# Actuator_control_v6.net
KiCad netlist of a schematic drawn in EAGLE
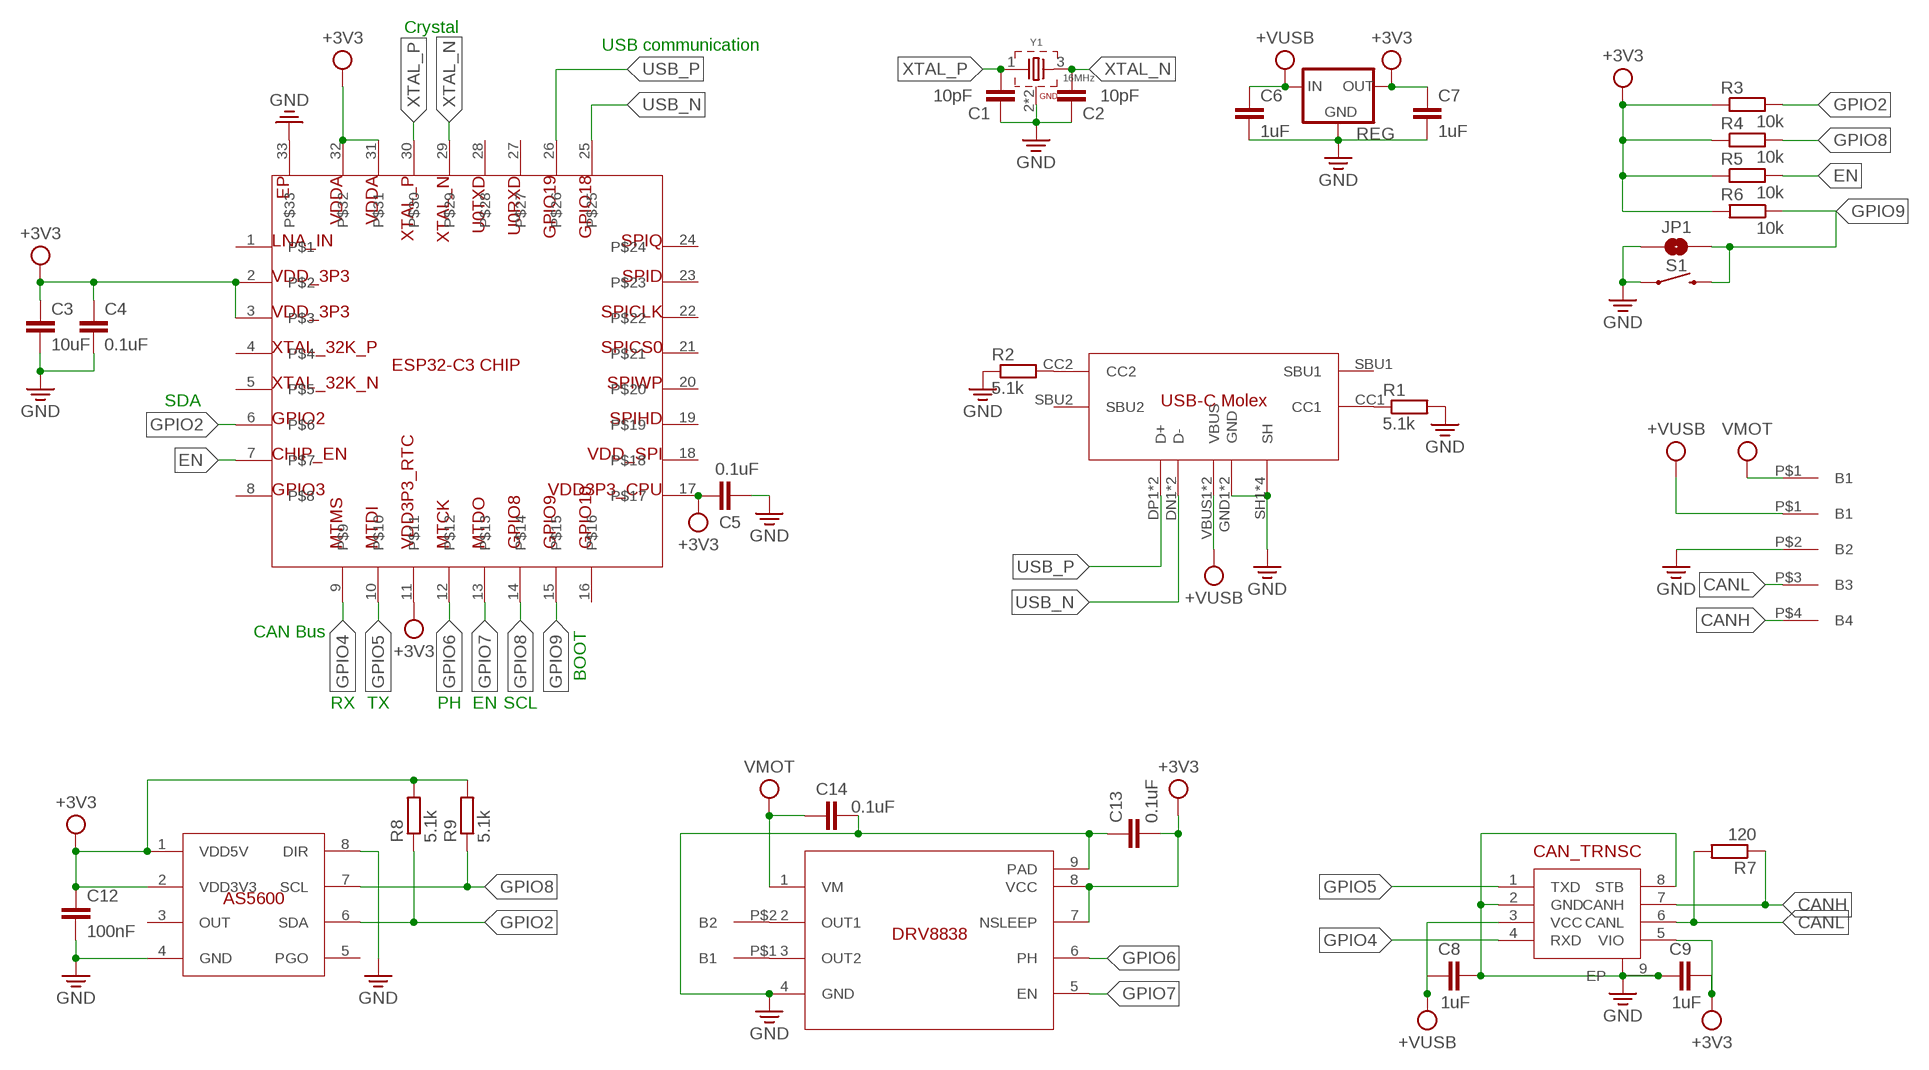
[diagram p0: schematic, sheet 1]

(export (version "E")
  (design (tool "Eeschema 10.0.6"))
  (components
    (comp (ref "AS5600")
      (value "AS5600")
      (footprint "eagle-import:SOIC127P600X175-8N")
      (libsource (lib "eagle-import") (part "AS5600"))
    )
    (comp (ref "C1")
      (value "10pF")
      (footprint "eagle-import:C0402")
      (libsource (lib "eagle-import") (part "C-EUC0402"))
    )
    (comp (ref "C2")
      (value "10pF")
      (footprint "eagle-import:C0402")
      (libsource (lib "eagle-import") (part "C-EUC0402"))
    )
    (comp (ref "C3")
      (value "10uF")
      (footprint "eagle-import:C0402")
      (libsource (lib "eagle-import") (part "C-EUC0402"))
    )
    (comp (ref "C4")
      (value "0.1uF")
      (footprint "eagle-import:C0402")
      (libsource (lib "eagle-import") (part "C-EUC0402"))
    )
    (comp (ref "C5")
      (value "0.1uF")
      (footprint "eagle-import:C0402")
      (libsource (lib "eagle-import") (part "C-EUC0402"))
    )
    (comp (ref "C6")
      (value "1uF")
      (footprint "eagle-import:C0402")
      (libsource (lib "eagle-import") (part "C-EUC0402"))
    )
    (comp (ref "C7")
      (value "1uF")
      (footprint "eagle-import:C0402")
      (libsource (lib "eagle-import") (part "C-EUC0402"))
    )
    (comp (ref "C8")
      (value "1uF")
      (footprint "eagle-import:C0402")
      (libsource (lib "eagle-import") (part "C-EUC0402"))
    )
    (comp (ref "C9")
      (value "1uF")
      (footprint "eagle-import:C0402")
      (libsource (lib "eagle-import") (part "C-EUC0402"))
    )
    (comp (ref "C12")
      (value "100nF")
      (footprint "eagle-import:C0402")
      (libsource (lib "eagle-import") (part "C-EUC0402"))
    )
    (comp (ref "C13")
      (value "0.1uF")
      (footprint "eagle-import:C0402")
      (libsource (lib "eagle-import") (part "C-EUC0402"))
    )
    (comp (ref "C14")
      (value "0.1uF")
      (footprint "eagle-import:C0402")
      (libsource (lib "eagle-import") (part "C-EUC0402"))
    )
    (comp (ref "CAN")
      (value "CAN_TRNSC")
      (footprint "eagle-import:SON65P300X300X75-9T160X240N")
      (libsource (lib "eagle-import") (part "CAN_TRNSC"))
    )
    (comp (ref "DRV8838")
      (value "DRV8838")
      (footprint "eagle-import:SON50P200X200X80-9T90X160N")
      (libsource (lib "eagle-import") (part "DRV8838"))
    )
    (comp (ref "ESP32")
      (value "ESP32-C3CHIP")
      (footprint "eagle-import:ESP32-C3_CHIP")
      (libsource (lib "eagle-import") (part "ESP32-C3CHIP"))
    )
    (comp (ref "JP1")
      (value "JUMPER-SMT_2_NO_SILK")
      (footprint "eagle-import:SMT-JUMPER_2_NO_SILK")
      (libsource (lib "eagle-import") (part "JUMPER-SMT_2_NO_SILK"))
    )
    (comp (ref "R1")
      (value "5.1k")
      (footprint "eagle-import:R0402")
      (libsource (lib "eagle-import") (part "R-EU_R0402"))
    )
    (comp (ref "R2")
      (value "5.1k")
      (footprint "eagle-import:R0402")
      (libsource (lib "eagle-import") (part "R-EU_R0402"))
    )
    (comp (ref "R3")
      (value "10k")
      (footprint "eagle-import:R0402")
      (libsource (lib "eagle-import") (part "R-EU_R0402"))
    )
    (comp (ref "R4")
      (value "10k")
      (footprint "eagle-import:R0402")
      (libsource (lib "eagle-import") (part "R-EU_R0402"))
    )
    (comp (ref "R5")
      (value "10k")
      (footprint "eagle-import:R0402")
      (libsource (lib "eagle-import") (part "R-EU_R0402"))
    )
    (comp (ref "R6")
      (value "10k")
      (footprint "eagle-import:R0402")
      (libsource (lib "eagle-import") (part "R-EU_R0402"))
    )
    (comp (ref "R7")
      (value "120")
      (footprint "eagle-import:R0402")
      (libsource (lib "eagle-import") (part "R-EU_R0402"))
    )
    (comp (ref "R8")
      (value "5.1k")
      (footprint "eagle-import:R0402")
      (libsource (lib "eagle-import") (part "R-EU_R0402"))
    )
    (comp (ref "R9")
      (value "5.1k")
      (footprint "eagle-import:R0402")
      (libsource (lib "eagle-import") (part "R-EU_R0402"))
    )
    (comp (ref "REG")
      (value "XC63FPM")
      (footprint "eagle-import:SOT23")
      (libsource (lib "eagle-import") (part "XC63FPM"))
    )
    (comp (ref "S1")
      (value "MOMENTARY-SWITCH-SPST-SMD-6.0X3.5MM")
      (footprint "eagle-import:TACTILE_SWITCH_SMD_6.0X3.5MM")
      (libsource (lib "eagle-import") (part "MOMENTARY-SWITCH-SPST-SMD-6.0X3.5MM"))
    )
    (comp (ref "U$3")
      (value "USB-CMOLEX")
      (footprint "eagle-import:USB-CMOLEX")
      (libsource (lib "eagle-import") (part "USB-CMOLEX"))
    )
    (comp (ref "U$6")
      (value "BREAKOUT_44-SMD2.54")
      (footprint "eagle-import:BREAKOUT_4_SMD_2.54")
      (libsource (lib "eagle-import") (part "BREAKOUT_44-SMD2.54"))
    )
    (comp (ref "U$7")
      (value "BREAKOUT_11-SMD-2.54")
      (footprint "eagle-import:BREAKOUT_1_SMD_2.54")
      (libsource (lib "eagle-import") (part "BREAKOUT_11-SMD-2.54"))
    )
    (comp (ref "U$8")
      (value "BREAKOUT_22-THT")
      (footprint "eagle-import:BREAKOUT_2_THT")
      (libsource (lib "eagle-import") (part "BREAKOUT_22-THT"))
    )
    (comp (ref "Y1")
      (value "16MHz")
      (footprint "eagle-import:WE-XTAL_CFPX-180")
      (fields (field (name "TOLERANCE") "±50ppm"))
      (libsource (lib "eagle-import") (part "WE-XTAL_CFPX-180_830035264"))
    )
  )
  (nets
    (net (code "1") (name "+3V3") (class "Default")
      (node (ref "AS5600") (pin "1") (pinfunction "VDD5V_1") (pintype "power_in"))
      (node (ref "AS5600") (pin "2") (pinfunction "VDD3V3_2") (pintype "power_in"))
      (node (ref "C12") (pin "1") (pinfunction "1_1") (pintype "passive"))
      (node (ref "C13") (pin "2") (pinfunction "2_2") (pintype "passive"))
      (node (ref "C3") (pin "1") (pinfunction "1_1") (pintype "passive"))
      (node (ref "C4") (pin "1") (pinfunction "1_1") (pintype "passive"))
      (node (ref "C5") (pin "2") (pinfunction "2_2") (pintype "passive"))
      (node (ref "C7") (pin "1") (pinfunction "1_1") (pintype "passive"))
      (node (ref "C9") (pin "2") (pinfunction "2_2") (pintype "passive"))
      (node (ref "CAN") (pin "5") (pinfunction "VIO_5") (pintype "bidirectional"))
      (node (ref "DRV8838") (pin "7") (pinfunction "NSLEEP_7") (pintype "bidirectional"))
      (node (ref "DRV8838") (pin "8") (pinfunction "VCC_8") (pintype "bidirectional"))
      (node (ref "ESP32") (pin "11") (pinfunction "P$11_11") (pintype "bidirectional"))
      (node (ref "ESP32") (pin "17") (pinfunction "P$17_17") (pintype "bidirectional"))
      (node (ref "ESP32") (pin "2") (pinfunction "P$2_2") (pintype "bidirectional"))
      (node (ref "ESP32") (pin "3") (pinfunction "P$3_3") (pintype "bidirectional"))
      (node (ref "ESP32") (pin "31") (pinfunction "P$31_31") (pintype "bidirectional"))
      (node (ref "ESP32") (pin "32") (pinfunction "P$32_32") (pintype "bidirectional"))
      (node (ref "R3") (pin "1") (pinfunction "1_1") (pintype "passive"))
      (node (ref "R4") (pin "1") (pinfunction "1_1") (pintype "passive"))
      (node (ref "R5") (pin "1") (pinfunction "1_1") (pintype "passive"))
      (node (ref "R6") (pin "2") (pinfunction "2_2") (pintype "passive"))
      (node (ref "R8") (pin "2") (pinfunction "2_2") (pintype "passive"))
      (node (ref "R9") (pin "2") (pinfunction "2_2") (pintype "passive"))
      (node (ref "REG") (pin "2") (pinfunction "OUT_2") (pintype "passive"))
    )
    (net (code "2") (name "+VUSB") (class "Default")
      (node (ref "C6") (pin "1") (pinfunction "1_1") (pintype "passive"))
      (node (ref "C8") (pin "1") (pinfunction "1_1") (pintype "passive"))
      (node (ref "CAN") (pin "3") (pinfunction "VCC_3") (pintype "power_in"))
      (node (ref "REG") (pin "3") (pinfunction "IN_3") (pintype "input"))
      (node (ref "U$3") (pin "VBUS1") (pinfunction "VBUS_VBUS1") (pintype "power_in"))
      (node (ref "U$3") (pin "VBUS2") (pinfunction "VBUS_VBUS2") (pintype "power_in"))
      (node (ref "U$6") (pin "P$1") (pinfunction "B1_P$1") (pintype "bidirectional"))
    )
    (net (code "3") (name "/OUT") (class "Default")
      (node (ref "AS5600") (pin "3") (pinfunction "OUT_3") (pintype "power_in"))
    )
    (net (code "4") (name "/PGO") (class "Default")
      (node (ref "AS5600") (pin "5") (pinfunction "PGO_5") (pintype "power_in"))
    )
    (net (code "5") (name "CANH") (class "Default")
      (node (ref "CAN") (pin "7") (pinfunction "CANH_7") (pintype "bidirectional"))
      (node (ref "R7") (pin "1") (pinfunction "1_1") (pintype "passive"))
      (node (ref "U$6") (pin "P$4") (pinfunction "B4_P$4") (pintype "bidirectional"))
    )
    (net (code "6") (name "CANL") (class "Default")
      (node (ref "CAN") (pin "6") (pinfunction "CANL_6") (pintype "bidirectional"))
      (node (ref "R7") (pin "2") (pinfunction "2_2") (pintype "passive"))
      (node (ref "U$6") (pin "P$3") (pinfunction "B3_P$3") (pintype "bidirectional"))
    )
    (net (code "7") (name "EN") (class "Default")
      (node (ref "ESP32") (pin "7") (pinfunction "P$7_7") (pintype "bidirectional"))
      (node (ref "R5") (pin "2") (pinfunction "2_2") (pintype "passive"))
    )
    (net (code "8") (name "GND") (class "Default")
      (node (ref "AS5600") (pin "4") (pinfunction "GND_4") (pintype "power_in"))
      (node (ref "AS5600") (pin "8") (pinfunction "DIR_8") (pintype "power_in"))
      (node (ref "C1") (pin "1") (pinfunction "1_1") (pintype "passive"))
      (node (ref "C12") (pin "2") (pinfunction "2_2") (pintype "passive"))
      (node (ref "C13") (pin "1") (pinfunction "1_1") (pintype "passive"))
      (node (ref "C14") (pin "2") (pinfunction "2_2") (pintype "passive"))
      (node (ref "C2") (pin "1") (pinfunction "1_1") (pintype "passive"))
      (node (ref "C3") (pin "2") (pinfunction "2_2") (pintype "passive"))
      (node (ref "C4") (pin "2") (pinfunction "2_2") (pintype "passive"))
      (node (ref "C5") (pin "1") (pinfunction "1_1") (pintype "passive"))
      (node (ref "C6") (pin "2") (pinfunction "2_2") (pintype "passive"))
      (node (ref "C7") (pin "2") (pinfunction "2_2") (pintype "passive"))
      (node (ref "C8") (pin "2") (pinfunction "2_2") (pintype "passive"))
      (node (ref "C9") (pin "1") (pinfunction "1_1") (pintype "passive"))
      (node (ref "CAN") (pin "2") (pinfunction "GND_2") (pintype "power_in"))
      (node (ref "CAN") (pin "8") (pinfunction "STB_8") (pintype "bidirectional"))
      (node (ref "CAN") (pin "9") (pinfunction "EP_9") (pintype "power_in"))
      (node (ref "DRV8838") (pin "4") (pinfunction "GND_4") (pintype "bidirectional"))
      (node (ref "DRV8838") (pin "9") (pinfunction "PAD_9") (pintype "bidirectional"))
      (node (ref "ESP32") (pin "33") (pinfunction "P$33_33") (pintype "bidirectional"))
      (node (ref "JP1") (pin "1") (pinfunction "1_1") (pintype "passive"))
      (node (ref "R1") (pin "2") (pinfunction "2_2") (pintype "passive"))
      (node (ref "R2") (pin "1") (pinfunction "1_1") (pintype "passive"))
      (node (ref "REG") (pin "1") (pinfunction "GND_1") (pintype "input"))
      (node (ref "S1") (pin "1") (pinfunction "1_1") (pintype "passive"))
      (node (ref "U$3") (pin "GND1") (pinfunction "GND_GND1") (pintype "power_in"))
      (node (ref "U$3") (pin "GND2") (pinfunction "GND_GND2") (pintype "power_in"))
      (node (ref "U$3") (pin "SH1") (pinfunction "SH_SH1") (pintype "power_in"))
      (node (ref "U$3") (pin "SH2") (pinfunction "SH_SH2") (pintype "power_in"))
      (node (ref "U$3") (pin "SH3") (pinfunction "SH_SH3") (pintype "power_in"))
      (node (ref "U$3") (pin "SH4") (pinfunction "SH_SH4") (pintype "power_in"))
      (node (ref "U$6") (pin "P$2") (pinfunction "B2_P$2") (pintype "bidirectional"))
      (node (ref "Y1") (pin "2") (pinfunction "GND_2") (pintype "passive"))
      (node (ref "Y1") (pin "4") (pinfunction "GND_4") (pintype "passive"))
    )
    (net (code "9") (name "GPIO2") (class "Default")
      (node (ref "AS5600") (pin "6") (pinfunction "SDA_6") (pintype "power_in"))
      (node (ref "ESP32") (pin "6") (pinfunction "P$6_6") (pintype "bidirectional"))
      (node (ref "R3") (pin "2") (pinfunction "2_2") (pintype "passive"))
      (node (ref "R8") (pin "1") (pinfunction "1_1") (pintype "passive"))
    )
    (net (code "10") (name "GPIO4") (class "Default")
      (node (ref "CAN") (pin "4") (pinfunction "RXD_4") (pintype "bidirectional"))
      (node (ref "ESP32") (pin "9") (pinfunction "P$9_9") (pintype "bidirectional"))
    )
    (net (code "11") (name "GPIO5") (class "Default")
      (node (ref "CAN") (pin "1") (pinfunction "TXD_1") (pintype "bidirectional"))
      (node (ref "ESP32") (pin "10") (pinfunction "P$10_10") (pintype "bidirectional"))
    )
    (net (code "12") (name "GPIO6") (class "Default")
      (node (ref "DRV8838") (pin "6") (pinfunction "PH_6") (pintype "bidirectional"))
      (node (ref "ESP32") (pin "12") (pinfunction "P$12_12") (pintype "bidirectional"))
    )
    (net (code "13") (name "GPIO7") (class "Default")
      (node (ref "DRV8838") (pin "5") (pinfunction "EN_5") (pintype "bidirectional"))
      (node (ref "ESP32") (pin "13") (pinfunction "P$13_13") (pintype "bidirectional"))
    )
    (net (code "14") (name "GPIO8") (class "Default")
      (node (ref "AS5600") (pin "7") (pinfunction "SCL_7") (pintype "power_in"))
      (node (ref "ESP32") (pin "14") (pinfunction "P$14_14") (pintype "bidirectional"))
      (node (ref "R4") (pin "2") (pinfunction "2_2") (pintype "passive"))
      (node (ref "R9") (pin "1") (pinfunction "1_1") (pintype "passive"))
    )
    (net (code "15") (name "GPIO9") (class "Default")
      (node (ref "ESP32") (pin "15") (pinfunction "P$15_15") (pintype "bidirectional"))
      (node (ref "JP1") (pin "2") (pinfunction "2_2") (pintype "passive"))
      (node (ref "R6") (pin "1") (pinfunction "1_1") (pintype "passive"))
      (node (ref "S1") (pin "2") (pinfunction "2_2") (pintype "passive"))
    )
    (net (code "16") (name "Net-(DRV8838-OUT1)") (class "Default")
      (node (ref "DRV8838") (pin "2") (pinfunction "OUT1_2") (pintype "bidirectional"))
      (node (ref "U$8") (pin "P$2") (pinfunction "B2_P$2") (pintype "bidirectional"))
    )
    (net (code "17") (name "Net-(DRV8838-OUT2)") (class "Default")
      (node (ref "DRV8838") (pin "3") (pinfunction "OUT2_3") (pintype "bidirectional"))
      (node (ref "U$8") (pin "P$1") (pinfunction "B1_P$1") (pintype "bidirectional"))
    )
    (net (code "18") (name "Net-(R1-Pad1)") (class "Default")
      (node (ref "R1") (pin "1") (pinfunction "1_1") (pintype "passive"))
      (node (ref "U$3") (pin "CC1") (pinfunction "CC1_CC1") (pintype "bidirectional"))
    )
    (net (code "19") (name "Net-(R2-Pad2)") (class "Default")
      (node (ref "R2") (pin "2") (pinfunction "2_2") (pintype "passive"))
      (node (ref "U$3") (pin "CC2") (pinfunction "CC2_CC2") (pintype "bidirectional"))
    )
    (net (code "20") (name "USB_N") (class "Default")
      (node (ref "ESP32") (pin "25") (pinfunction "P$25_25") (pintype "bidirectional"))
      (node (ref "U$3") (pin "DN1") (pinfunction "D-_DN1") (pintype "bidirectional"))
      (node (ref "U$3") (pin "DN2") (pinfunction "D-_DN2") (pintype "bidirectional"))
    )
    (net (code "21") (name "USB_P") (class "Default")
      (node (ref "ESP32") (pin "26") (pinfunction "P$26_26") (pintype "bidirectional"))
      (node (ref "U$3") (pin "DP1") (pinfunction "D+_DP1") (pintype "bidirectional"))
      (node (ref "U$3") (pin "DP2") (pinfunction "D+_DP2") (pintype "bidirectional"))
    )
    (net (code "22") (name "VMOT") (class "Default")
      (node (ref "C14") (pin "1") (pinfunction "1_1") (pintype "passive"))
      (node (ref "DRV8838") (pin "1") (pinfunction "VM_1") (pintype "bidirectional"))
      (node (ref "U$7") (pin "P$1") (pinfunction "B1_P$1") (pintype "bidirectional"))
    )
    (net (code "23") (name "XTAL_N") (class "Default")
      (node (ref "C2") (pin "2") (pinfunction "2_2") (pintype "passive"))
      (node (ref "ESP32") (pin "29") (pinfunction "P$29_29") (pintype "bidirectional"))
      (node (ref "Y1") (pin "3") (pinfunction "2_3") (pintype "passive"))
    )
    (net (code "24") (name "XTAL_P") (class "Default")
      (node (ref "C1") (pin "2") (pinfunction "2_2") (pintype "passive"))
      (node (ref "ESP32") (pin "30") (pinfunction "P$30_30") (pintype "bidirectional"))
      (node (ref "Y1") (pin "1") (pinfunction "1_1") (pintype "passive"))
    )
    (net (code "25") (name "unconnected-(ESP32-P$1-Pad1)") (class "Default")
      (node (ref "ESP32") (pin "1") (pinfunction "P$1_1") (pintype "bidirectional"))
    )
    (net (code "26") (name "unconnected-(ESP32-P$4-Pad4)") (class "Default")
      (node (ref "ESP32") (pin "4") (pinfunction "P$4_4") (pintype "bidirectional"))
    )
    (net (code "27") (name "unconnected-(ESP32-P$5-Pad5)") (class "Default")
      (node (ref "ESP32") (pin "5") (pinfunction "P$5_5") (pintype "bidirectional"))
    )
    (net (code "28") (name "unconnected-(ESP32-P$8-Pad8)") (class "Default")
      (node (ref "ESP32") (pin "8") (pinfunction "P$8_8") (pintype "bidirectional"))
    )
    (net (code "29") (name "unconnected-(ESP32-P$16-Pad16)") (class "Default")
      (node (ref "ESP32") (pin "16") (pinfunction "P$16_16") (pintype "bidirectional"))
    )
    (net (code "30") (name "unconnected-(ESP32-P$18-Pad18)") (class "Default")
      (node (ref "ESP32") (pin "18") (pinfunction "P$18_18") (pintype "bidirectional"))
    )
    (net (code "31") (name "unconnected-(ESP32-P$19-Pad19)") (class "Default")
      (node (ref "ESP32") (pin "19") (pinfunction "P$19_19") (pintype "bidirectional"))
    )
    (net (code "32") (name "unconnected-(ESP32-P$20-Pad20)") (class "Default")
      (node (ref "ESP32") (pin "20") (pinfunction "P$20_20") (pintype "bidirectional"))
    )
    (net (code "33") (name "unconnected-(ESP32-P$21-Pad21)") (class "Default")
      (node (ref "ESP32") (pin "21") (pinfunction "P$21_21") (pintype "bidirectional"))
    )
    (net (code "34") (name "unconnected-(ESP32-P$22-Pad22)") (class "Default")
      (node (ref "ESP32") (pin "22") (pinfunction "P$22_22") (pintype "bidirectional"))
    )
    (net (code "35") (name "unconnected-(ESP32-P$23-Pad23)") (class "Default")
      (node (ref "ESP32") (pin "23") (pinfunction "P$23_23") (pintype "bidirectional"))
    )
    (net (code "36") (name "unconnected-(ESP32-P$24-Pad24)") (class "Default")
      (node (ref "ESP32") (pin "24") (pinfunction "P$24_24") (pintype "bidirectional"))
    )
    (net (code "37") (name "unconnected-(ESP32-P$27-Pad27)") (class "Default")
      (node (ref "ESP32") (pin "27") (pinfunction "P$27_27") (pintype "bidirectional"))
    )
    (net (code "38") (name "unconnected-(ESP32-P$28-Pad28)") (class "Default")
      (node (ref "ESP32") (pin "28") (pinfunction "P$28_28") (pintype "bidirectional"))
    )
    (net (code "39") (name "unconnected-(U$3-PadSBU1)") (class "Default")
      (node (ref "U$3") (pin "SBU1") (pinfunction "SBU1_SBU1") (pintype "bidirectional"))
    )
    (net (code "40") (name "unconnected-(U$3-PadSBU2)") (class "Default")
      (node (ref "U$3") (pin "SBU2") (pinfunction "SBU2_SBU2") (pintype "bidirectional"))
    )
  )
)
